# NIXIE_1.net
KiCad netlist of a schematic drawn in Altium Designer
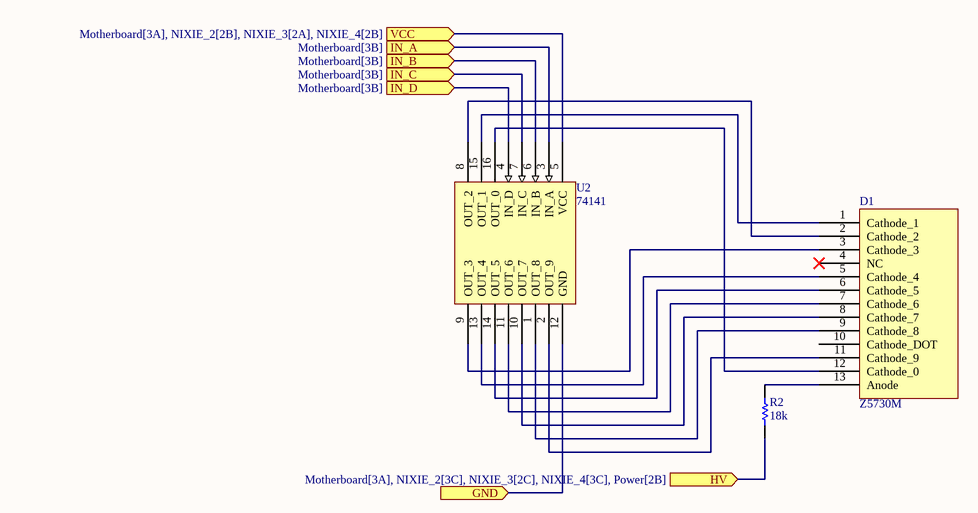
[diagram p0: NIXIE_1.SchDoc]

(export (version "E")
  (design (tool "Eeschema 10.0.6"))
  (components
    (comp (ref "D1") (value "Z5730M") (footprint "Z5730M") (libsource (lib "Z5730M") (part "Z5730M")))
    (comp (ref "R2")
      (value "18k")
      (footprint "RESC2013X60X40LL20T25")
      (fields (field (name "MANUFACTURER") "Panasonic") (field (name "PART NUMBER") "ERA6AEB183V"))
      (libsource (lib "Altium Content Vault") (part "RES"))
    )
    (comp (ref "U2") (value "74141") (footprint "DIP-16") (libsource (lib "Z5730M") (part "74141")))
  )
  (nets
    (net (code "1") (name "/GND") (class "Default")
      (node (ref "U2") (pin "12") (pinfunction "GND_12") (pintype "power_in"))
    )
    (net (code "2") (name "/HV") (class "Default")
      (node (ref "R2") (pin "1") (pinfunction "1_1") (pintype "passive"))
    )
    (net (code "3") (name "/IN_A") (class "Default")
      (node (ref "U2") (pin "3") (pinfunction "IN_A_3") (pintype "input"))
    )
    (net (code "4") (name "/IN_B") (class "Default")
      (node (ref "U2") (pin "6") (pinfunction "IN_B_6") (pintype "input"))
    )
    (net (code "5") (name "/IN_C") (class "Default")
      (node (ref "U2") (pin "7") (pinfunction "IN_C_7") (pintype "input"))
    )
    (net (code "6") (name "/IN_D") (class "Default")
      (node (ref "U2") (pin "4") (pinfunction "IN_D_4") (pintype "input"))
    )
    (net (code "7") (name "/VCC") (class "Default")
      (node (ref "U2") (pin "5") (pinfunction "VCC_5") (pintype "power_in"))
    )
    (net (code "8") (name "Net-(D1-Anode)") (class "Default")
      (node (ref "D1") (pin "13") (pinfunction "Anode_13") (pintype "passive"))
      (node (ref "R2") (pin "2") (pinfunction "2_2") (pintype "passive"))
    )
    (net (code "9") (name "Net-(D1-Cathode_0)") (class "Default")
      (node (ref "D1") (pin "12") (pinfunction "Cathode_0_12") (pintype "passive"))
      (node (ref "U2") (pin "16") (pinfunction "OUT_0_16") (pintype "open_collector"))
    )
    (net (code "10") (name "Net-(D1-Cathode_1)") (class "Default")
      (node (ref "D1") (pin "1") (pinfunction "Cathode_1_1") (pintype "passive"))
      (node (ref "U2") (pin "15") (pinfunction "OUT_1_15") (pintype "open_collector"))
    )
    (net (code "11") (name "Net-(D1-Cathode_2)") (class "Default")
      (node (ref "D1") (pin "2") (pinfunction "Cathode_2_2") (pintype "passive"))
      (node (ref "U2") (pin "8") (pinfunction "OUT_2_8") (pintype "open_collector"))
    )
    (net (code "12") (name "Net-(D1-Cathode_3)") (class "Default")
      (node (ref "D1") (pin "3") (pinfunction "Cathode_3_3") (pintype "passive"))
      (node (ref "U2") (pin "9") (pinfunction "OUT_3_9") (pintype "open_collector"))
    )
    (net (code "13") (name "Net-(D1-Cathode_4)") (class "Default")
      (node (ref "D1") (pin "5") (pinfunction "Cathode_4_5") (pintype "passive"))
      (node (ref "U2") (pin "13") (pinfunction "OUT_4_13") (pintype "open_collector"))
    )
    (net (code "14") (name "Net-(D1-Cathode_5)") (class "Default")
      (node (ref "D1") (pin "6") (pinfunction "Cathode_5_6") (pintype "passive"))
      (node (ref "U2") (pin "14") (pinfunction "OUT_5_14") (pintype "open_collector"))
    )
    (net (code "15") (name "Net-(D1-Cathode_6)") (class "Default")
      (node (ref "D1") (pin "7") (pinfunction "Cathode_6_7") (pintype "passive"))
      (node (ref "U2") (pin "11") (pinfunction "OUT_6_11") (pintype "open_collector"))
    )
    (net (code "16") (name "Net-(D1-Cathode_7)") (class "Default")
      (node (ref "D1") (pin "8") (pinfunction "Cathode_7_8") (pintype "passive"))
      (node (ref "U2") (pin "10") (pinfunction "OUT_7_10") (pintype "open_collector"))
    )
    (net (code "17") (name "Net-(D1-Cathode_8)") (class "Default")
      (node (ref "D1") (pin "9") (pinfunction "Cathode_8_9") (pintype "passive"))
      (node (ref "U2") (pin "1") (pinfunction "OUT_8_1") (pintype "open_collector"))
    )
    (net (code "18") (name "Net-(D1-Cathode_9)") (class "Default")
      (node (ref "D1") (pin "11") (pinfunction "Cathode_9_11") (pintype "passive"))
      (node (ref "U2") (pin "2") (pinfunction "OUT_9_2") (pintype "open_collector"))
    )
    (net (code "19") (name "unconnected-(D1-Cathode_DOT-Pad10)") (class "Default")
      (node (ref "D1") (pin "10") (pinfunction "Cathode_DOT_10") (pintype "passive"))
    )
    (net (code "20") (name "unconnected-(D1-NC-Pad4)") (class "Default")
      (node (ref "D1") (pin "4") (pinfunction "NC_4") (pintype "passive+no_connect"))
    )
  )
)
